# ESP8266Controller.net
KiCad netlist of a schematic drawn in EAGLE
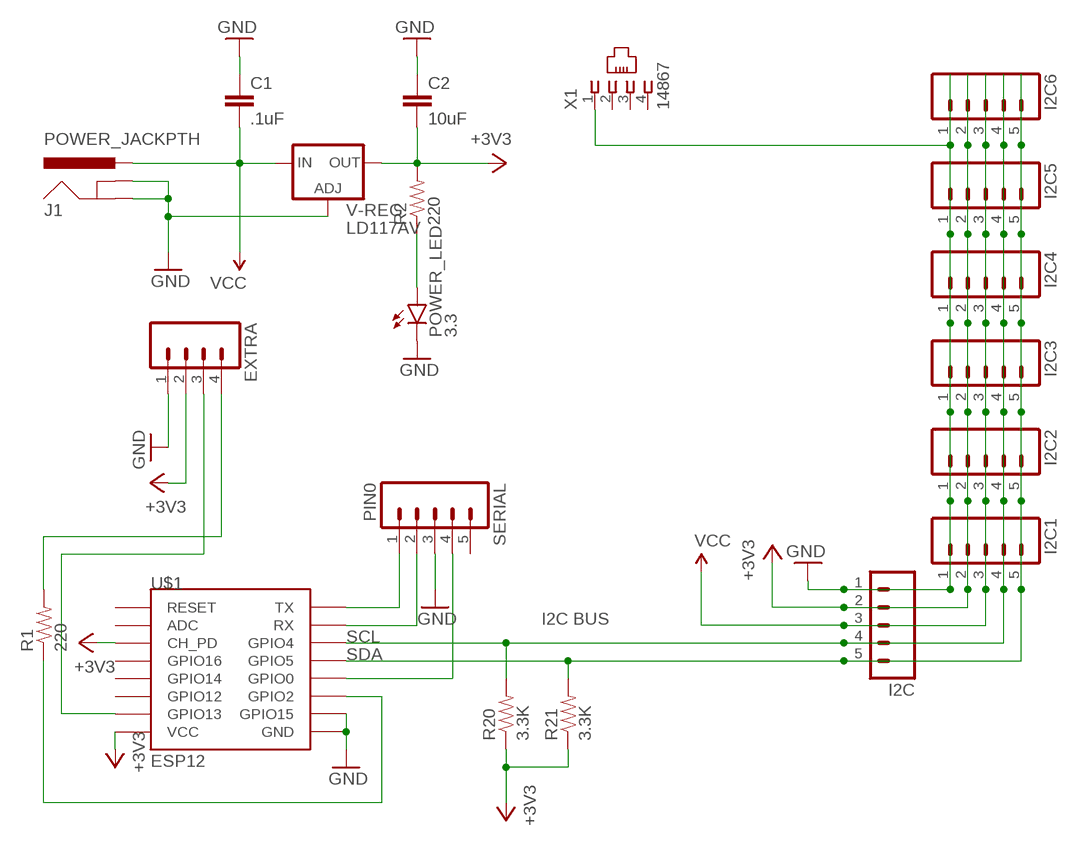
[diagram p0: schematic, sheet 1]

(export (version "E")
  (design (tool "Eeschema 10.0.6"))
  (components
    (comp (ref "C1")
      (value ".1uF")
      (footprint "eagle-import:CAP-PTH-SMALL")
      (libsource (lib "eagle-import") (part "CAPPTH"))
    )
    (comp (ref "C2")
      (value "10uF")
      (footprint "eagle-import:CAP-PTH-SMALL")
      (libsource (lib "eagle-import") (part "CAPPTH"))
    )
    (comp (ref "EXTRA")
      (value "M04")
      (footprint "eagle-import:04P")
      (libsource (lib "eagle-import") (part "M04"))
    )
    (comp (ref "I2C")
      (value "M05")
      (footprint "eagle-import:05P")
      (libsource (lib "eagle-import") (part "M05"))
    )
    (comp (ref "I2C1")
      (value "M05")
      (footprint "eagle-import:05P")
      (libsource (lib "eagle-import") (part "M05"))
    )
    (comp (ref "I2C2")
      (value "M05")
      (footprint "eagle-import:05P")
      (libsource (lib "eagle-import") (part "M05"))
    )
    (comp (ref "I2C3")
      (value "M05")
      (footprint "eagle-import:05P")
      (libsource (lib "eagle-import") (part "M05"))
    )
    (comp (ref "I2C4")
      (value "M05")
      (footprint "eagle-import:05P")
      (libsource (lib "eagle-import") (part "M05"))
    )
    (comp (ref "I2C5")
      (value "M05")
      (footprint "eagle-import:05P")
      (libsource (lib "eagle-import") (part "M05"))
    )
    (comp (ref "I2C6")
      (value "M05")
      (footprint "eagle-import:05P")
      (libsource (lib "eagle-import") (part "M05"))
    )
    (comp (ref "J1")
      (value "POWER_JACKPTH")
      (footprint "eagle-import:POWER_JACK_PTH")
      (libsource (lib "eagle-import") (part "POWER_JACKPTH"))
    )
    (comp (ref "POWER_LED")
      (value "3.3")
      (footprint "eagle-import:LED5MM")
      (libsource (lib "eagle-import") (part "LED5MM"))
    )
    (comp (ref "R1")
      (value "220")
      (footprint "eagle-import:AXIAL-0.4")
      (libsource (lib "eagle-import") (part "RESISTORPTH-1/4W"))
    )
    (comp (ref "R2")
      (value "220")
      (footprint "eagle-import:AXIAL-0.4")
      (libsource (lib "eagle-import") (part "RESISTORPTH-1/4W"))
    )
    (comp (ref "R20")
      (value "3.3K")
      (footprint "eagle-import:AXIAL-0.4")
      (libsource (lib "eagle-import") (part "RESISTORPTH-1/4W"))
    )
    (comp (ref "R21")
      (value "3.3K")
      (footprint "eagle-import:AXIAL-0.4")
      (libsource (lib "eagle-import") (part "RESISTORPTH-1/4W"))
    )
    (comp (ref "SERIAL")
      (value "PIN0")
      (footprint "eagle-import:05P")
      (libsource (lib "eagle-import") (part "M05"))
    )
    (comp (ref "U$1")
      (value "ESP12")
      (footprint "eagle-import:ESP12")
      (libsource (lib "eagle-import") (part "ESP12"))
    )
    (comp (ref "V-REG")
      (value "LD117AV")
      (footprint "eagle-import:TO220L1")
      (libsource (lib "eagle-import") (part "LD117A?V"))
    )
    (comp (ref "X1")
      (value "14867")
      (footprint "eagle-import:14867")
      (libsource (lib "eagle-import") (part "14867"))
    )
  )
  (nets
    (net (code "1") (name "+3V3") (class "Default")
      (node (ref "C2") (pin "2") (pinfunction "2_2") (pintype "passive"))
      (node (ref "EXTRA") (pin "2") (pinfunction "2_2") (pintype "passive"))
      (node (ref "I2C") (pin "2") (pinfunction "2_2") (pintype "passive"))
      (node (ref "I2C1") (pin "2") (pinfunction "2_2") (pintype "passive"))
      (node (ref "I2C2") (pin "2") (pinfunction "2_2") (pintype "passive"))
      (node (ref "I2C3") (pin "2") (pinfunction "2_2") (pintype "passive"))
      (node (ref "I2C4") (pin "2") (pinfunction "2_2") (pintype "passive"))
      (node (ref "I2C5") (pin "2") (pinfunction "2_2") (pintype "passive"))
      (node (ref "I2C6") (pin "2") (pinfunction "2_2") (pintype "passive"))
      (node (ref "R2") (pin "P$2") (pinfunction "2_P$2") (pintype "passive"))
      (node (ref "R20") (pin "P$1") (pinfunction "1_P$1") (pintype "passive"))
      (node (ref "R21") (pin "P$1") (pinfunction "1_P$1") (pintype "passive"))
      (node (ref "U$1") (pin "CH_PD") (pinfunction "CH_PD_CH_PD") (pintype "bidirectional"))
      (node (ref "U$1") (pin "VCC") (pinfunction "VCC_VCC") (pintype "bidirectional"))
      (node (ref "V-REG") (pin "2") (pinfunction "OUT_2") (pintype "passive"))
    )
    (net (code "2") (name "/SCL") (class "Default")
      (node (ref "I2C") (pin "4") (pinfunction "4_4") (pintype "passive"))
      (node (ref "I2C1") (pin "4") (pinfunction "4_4") (pintype "passive"))
      (node (ref "I2C2") (pin "4") (pinfunction "4_4") (pintype "passive"))
      (node (ref "I2C3") (pin "4") (pinfunction "4_4") (pintype "passive"))
      (node (ref "I2C4") (pin "4") (pinfunction "4_4") (pintype "passive"))
      (node (ref "I2C5") (pin "4") (pinfunction "4_4") (pintype "passive"))
      (node (ref "I2C6") (pin "4") (pinfunction "4_4") (pintype "passive"))
      (node (ref "R20") (pin "P$2") (pinfunction "2_P$2") (pintype "passive"))
      (node (ref "U$1") (pin "GPIO4") (pinfunction "GPIO4_GPIO4") (pintype "bidirectional"))
    )
    (net (code "3") (name "/SDA") (class "Default")
      (node (ref "I2C") (pin "5") (pinfunction "5_5") (pintype "passive"))
      (node (ref "I2C1") (pin "5") (pinfunction "5_5") (pintype "passive"))
      (node (ref "I2C2") (pin "5") (pinfunction "5_5") (pintype "passive"))
      (node (ref "I2C3") (pin "5") (pinfunction "5_5") (pintype "passive"))
      (node (ref "I2C4") (pin "5") (pinfunction "5_5") (pintype "passive"))
      (node (ref "I2C5") (pin "5") (pinfunction "5_5") (pintype "passive"))
      (node (ref "I2C6") (pin "5") (pinfunction "5_5") (pintype "passive"))
      (node (ref "R21") (pin "P$2") (pinfunction "2_P$2") (pintype "passive"))
      (node (ref "U$1") (pin "GPIO5") (pinfunction "GPIO5_GPIO5") (pintype "bidirectional"))
    )
    (net (code "4") (name "GND") (class "Default")
      (node (ref "C1") (pin "1") (pinfunction "1_1") (pintype "passive"))
      (node (ref "C2") (pin "1") (pinfunction "1_1") (pintype "passive"))
      (node (ref "EXTRA") (pin "1") (pinfunction "1_1") (pintype "passive"))
      (node (ref "I2C") (pin "1") (pinfunction "1_1") (pintype "passive"))
      (node (ref "I2C1") (pin "1") (pinfunction "1_1") (pintype "passive"))
      (node (ref "I2C2") (pin "1") (pinfunction "1_1") (pintype "passive"))
      (node (ref "I2C3") (pin "1") (pinfunction "1_1") (pintype "passive"))
      (node (ref "I2C4") (pin "1") (pinfunction "1_1") (pintype "passive"))
      (node (ref "I2C5") (pin "1") (pinfunction "1_1") (pintype "passive"))
      (node (ref "I2C6") (pin "1") (pinfunction "1_1") (pintype "passive"))
      (node (ref "J1") (pin "GND") (pinfunction "GND_GND") (pintype "bidirectional"))
      (node (ref "J1") (pin "GNDBREAK") (pinfunction "GNDBREAK_GNDBREAK") (pintype "bidirectional"))
      (node (ref "POWER_LED") (pin "K") (pinfunction "C_K") (pintype "passive"))
      (node (ref "SERIAL") (pin "3") (pinfunction "3_3") (pintype "passive"))
      (node (ref "U$1") (pin "GND") (pinfunction "GND_GND") (pintype "bidirectional"))
      (node (ref "U$1") (pin "GPIO15") (pinfunction "GPIO15_GPIO15") (pintype "bidirectional"))
      (node (ref "V-REG") (pin "1") (pinfunction "ADJ_1") (pintype "input"))
      (node (ref "X1") (pin "1") (pinfunction "1_1") (pintype "passive"))
    )
    (net (code "5") (name "Net-(EXTRA-Pad3)") (class "Default")
      (node (ref "EXTRA") (pin "3") (pinfunction "3_3") (pintype "passive"))
      (node (ref "U$1") (pin "GPIO13") (pinfunction "GPIO13_GPIO13") (pintype "bidirectional"))
    )
    (net (code "6") (name "Net-(R1-1)") (class "Default")
      (node (ref "R1") (pin "P$1") (pinfunction "1_P$1") (pintype "passive"))
      (node (ref "U$1") (pin "GPIO2") (pinfunction "GPIO2_GPIO2") (pintype "bidirectional"))
    )
    (net (code "7") (name "Net-(R1-2)") (class "Default")
      (node (ref "EXTRA") (pin "4") (pinfunction "4_4") (pintype "passive"))
      (node (ref "R1") (pin "P$2") (pinfunction "2_P$2") (pintype "passive"))
    )
    (net (code "8") (name "Net-(R2-1)") (class "Default")
      (node (ref "POWER_LED") (pin "A") (pinfunction "A_A") (pintype "passive"))
      (node (ref "R2") (pin "P$1") (pinfunction "1_P$1") (pintype "passive"))
    )
    (net (code "9") (name "Net-(SERIAL-Pad1)") (class "Default")
      (node (ref "SERIAL") (pin "1") (pinfunction "1_1") (pintype "passive"))
      (node (ref "U$1") (pin "TX") (pinfunction "TX_TX") (pintype "bidirectional"))
    )
    (net (code "10") (name "Net-(SERIAL-Pad2)") (class "Default")
      (node (ref "SERIAL") (pin "2") (pinfunction "2_2") (pintype "passive"))
      (node (ref "U$1") (pin "RX") (pinfunction "RX_RX") (pintype "bidirectional"))
    )
    (net (code "11") (name "Net-(SERIAL-Pad4)") (class "Default")
      (node (ref "SERIAL") (pin "4") (pinfunction "4_4") (pintype "passive"))
      (node (ref "U$1") (pin "GPIO0") (pinfunction "GPIO0_GPIO0") (pintype "bidirectional"))
    )
    (net (code "12") (name "VCC") (class "Default")
      (node (ref "C1") (pin "2") (pinfunction "2_2") (pintype "passive"))
      (node (ref "I2C") (pin "3") (pinfunction "3_3") (pintype "passive"))
      (node (ref "I2C1") (pin "3") (pinfunction "3_3") (pintype "passive"))
      (node (ref "I2C2") (pin "3") (pinfunction "3_3") (pintype "passive"))
      (node (ref "I2C3") (pin "3") (pinfunction "3_3") (pintype "passive"))
      (node (ref "I2C4") (pin "3") (pinfunction "3_3") (pintype "passive"))
      (node (ref "I2C5") (pin "3") (pinfunction "3_3") (pintype "passive"))
      (node (ref "I2C6") (pin "3") (pinfunction "3_3") (pintype "passive"))
      (node (ref "J1") (pin "PWR") (pinfunction "PWR_PWR") (pintype "bidirectional"))
      (node (ref "V-REG") (pin "3") (pinfunction "IN_3") (pintype "input"))
    )
    (net (code "13") (name "unconnected-(SERIAL-Pad5)") (class "Default")
      (node (ref "SERIAL") (pin "5") (pinfunction "5_5") (pintype "passive"))
    )
    (net (code "14") (name "unconnected-(U$1-PadADC)") (class "Default")
      (node (ref "U$1") (pin "ADC") (pinfunction "ADC_ADC") (pintype "bidirectional"))
    )
    (net (code "15") (name "unconnected-(U$1-PadGPIO12)") (class "Default")
      (node (ref "U$1") (pin "GPIO12") (pinfunction "GPIO12_GPIO12") (pintype "bidirectional"))
    )
    (net (code "16") (name "unconnected-(U$1-PadGPIO14)") (class "Default")
      (node (ref "U$1") (pin "GPIO14") (pinfunction "GPIO14_GPIO14") (pintype "bidirectional"))
    )
    (net (code "17") (name "unconnected-(U$1-PadGPIO16)") (class "Default")
      (node (ref "U$1") (pin "GPIO16") (pinfunction "GPIO16_GPIO16") (pintype "bidirectional"))
    )
    (net (code "18") (name "unconnected-(U$1-PadRESET)") (class "Default")
      (node (ref "U$1") (pin "RESET") (pinfunction "RESET_RESET") (pintype "bidirectional"))
    )
    (net (code "19") (name "unconnected-(X1-Pad2)") (class "Default")
      (node (ref "X1") (pin "2") (pinfunction "2_2") (pintype "passive"))
    )
    (net (code "20") (name "unconnected-(X1-Pad3)") (class "Default")
      (node (ref "X1") (pin "3") (pinfunction "3_3") (pintype "passive"))
    )
    (net (code "21") (name "unconnected-(X1-Pad4)") (class "Default")
      (node (ref "X1") (pin "4") (pinfunction "4_4") (pintype "passive"))
    )
  )
)
